# 8_Conectors.net
KiCad netlist of a schematic drawn in Altium Designer
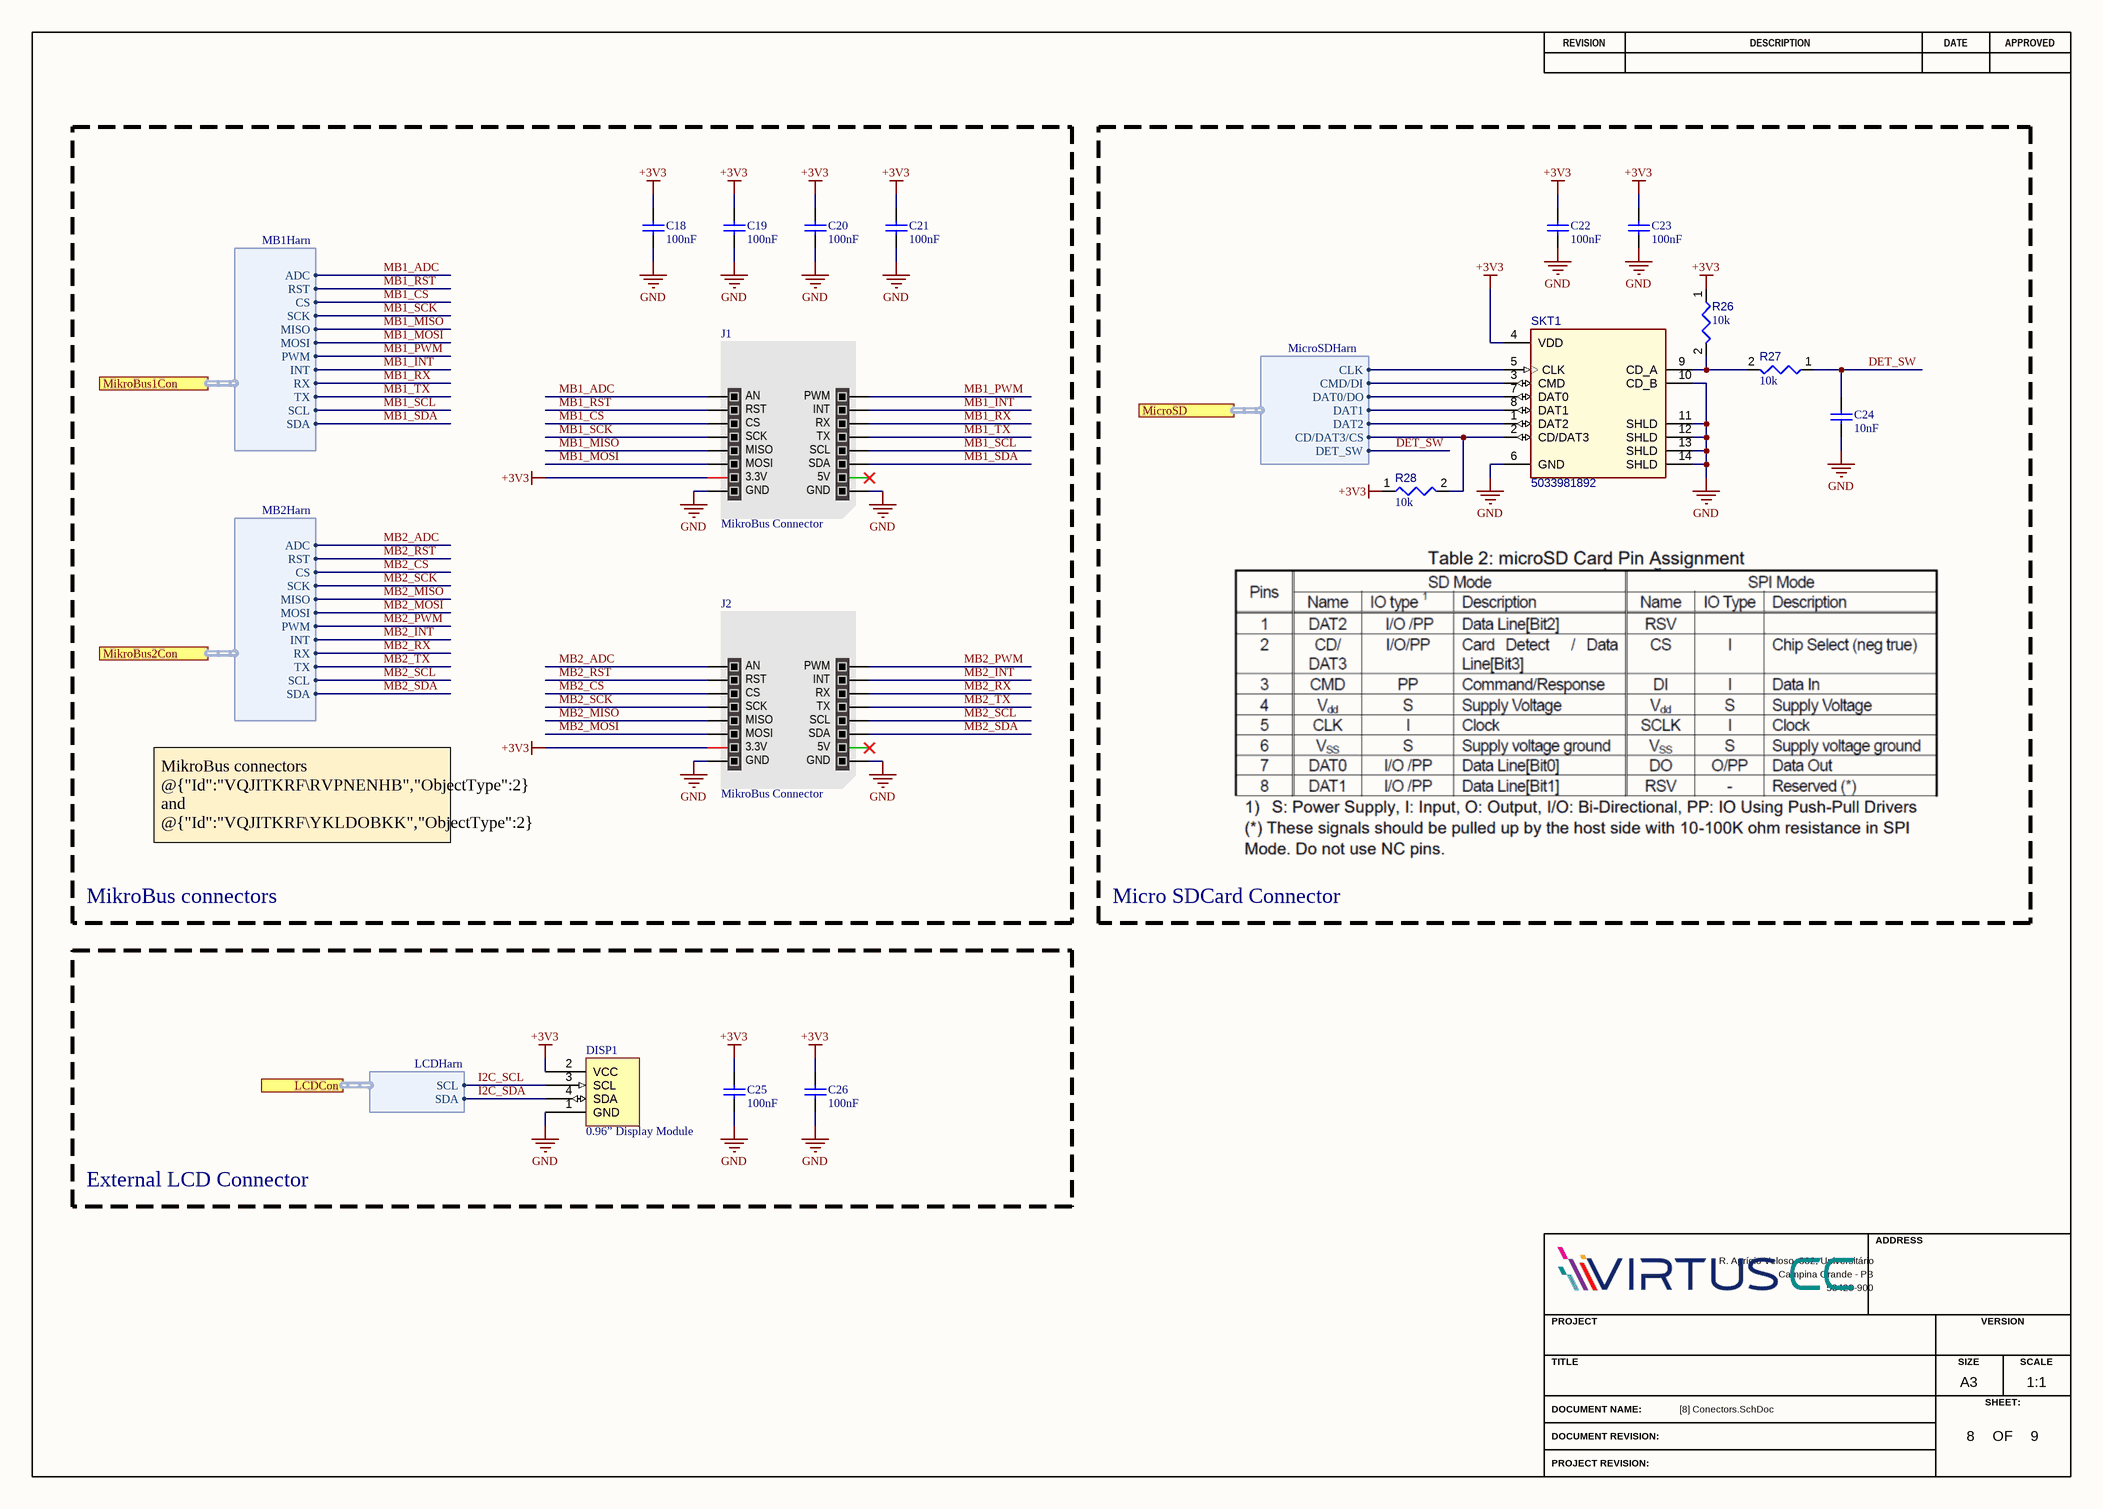
[diagram p0: [8] Conectors.SchDoc]

(export (version "E")
  (design (tool "Eeschema 10.0.6"))
  (components
    (comp (ref "C18")
      (value "100nF")
      (footprint "CAPC0603(1608)100_L")
      (description "Multilayer Ceramic Capacitor, 0.1 uF, 16 V, ± 20%, X7R, 0603 [1608 Metric]")
      (fields (field (name "TOLERANCE") "20%") (field (name "Comment") "VJ0603Y104MXJCW1BC"))
      (libsource (lib "UFCG - Universidade Federal de Campina Grande") (part "CAP"))
    )
    (comp (ref "C19")
      (value "100nF")
      (footprint "CAPC0603(1608)100_L")
      (description "Multilayer Ceramic Capacitor, 0.1 uF, 16 V, ± 20%, X7R, 0603 [1608 Metric]")
      (fields (field (name "TOLERANCE") "20%") (field (name "Comment") "VJ0603Y104MXJCW1BC"))
      (libsource (lib "UFCG - Universidade Federal de Campina Grande") (part "CAP"))
    )
    (comp (ref "C20")
      (value "100nF")
      (footprint "CAPC0603(1608)100_L")
      (description "Multilayer Ceramic Capacitor, 0.1 uF, 16 V, ± 20%, X7R, 0603 [1608 Metric]")
      (fields (field (name "TOLERANCE") "20%") (field (name "Comment") "VJ0603Y104MXJCW1BC"))
      (libsource (lib "UFCG - Universidade Federal de Campina Grande") (part "CAP"))
    )
    (comp (ref "C21")
      (value "100nF")
      (footprint "CAPC0603(1608)100_L")
      (description "Multilayer Ceramic Capacitor, 0.1 uF, 16 V, ± 20%, X7R, 0603 [1608 Metric]")
      (fields (field (name "TOLERANCE") "20%") (field (name "Comment") "VJ0603Y104MXJCW1BC"))
      (libsource (lib "UFCG - Universidade Federal de Campina Grande") (part "CAP"))
    )
    (comp (ref "C22")
      (value "100nF")
      (footprint "CAPC0603(1608)100_L")
      (description "Multilayer Ceramic Capacitor, 0.1 uF, 16 V, ± 20%, X7R, 0603 [1608 Metric]")
      (fields (field (name "TOLERANCE") "20%") (field (name "Comment") "VJ0603Y104MXJCW1BC"))
      (libsource (lib "UFCG - Universidade Federal de Campina Grande") (part "CAP"))
    )
    (comp (ref "C23")
      (value "100nF")
      (footprint "CAPC0603(1608)100_L")
      (description "Multilayer Ceramic Capacitor, 0.1 uF, 16 V, ± 20%, X7R, 0603 [1608 Metric]")
      (fields (field (name "TOLERANCE") "20%") (field (name "Comment") "VJ0603Y104MXJCW1BC"))
      (libsource (lib "UFCG - Universidade Federal de Campina Grande") (part "CAP"))
    )
    (comp (ref "C24")
      (value "10nF")
      (footprint "CAPC0603(1608)100_L")
      (description "Multilayer Ceramic Capacitor, 0.01 uF, 50 V, ± 10%, X7R, 0603 [1608 Metric]")
      (fields (field (name "VOLTAGE") "50V") (field (name "TOLERANCE") "10%"))
      (libsource (lib "UFCG - Universidade Federal de Campina Grande") (part "CAP"))
    )
    (comp (ref "C25")
      (value "100nF")
      (footprint "CAPC0603(1608)100_L")
      (description "Multilayer Ceramic Capacitor, 0.1 uF, 16 V, ± 20%, X7R, 0603 [1608 Metric]")
      (fields (field (name "TOLERANCE") "20%") (field (name "Comment") "VJ0603Y104MXJCW1BC"))
      (libsource (lib "UFCG - Universidade Federal de Campina Grande") (part "CAP"))
    )
    (comp (ref "C26")
      (value "100nF")
      (footprint "CAPC0603(1608)100_L")
      (description "Multilayer Ceramic Capacitor, 0.1 uF, 16 V, ± 20%, X7R, 0603 [1608 Metric]")
      (fields (field (name "TOLERANCE") "20%") (field (name "Comment") "VJ0603Y104MXJCW1BC"))
      (libsource (lib "UFCG - Universidade Federal de Campina Grande") (part "CAP"))
    )
    (comp (ref "DISP1")
      (value "0.96” Display Module")
      (footprint "New footprint 1")
      (description "0.96 Inch I2C OLED Display Module")
      (libsource (lib "UFCG - Universidade Federal de Campina Grande") (part "0.96{dblquote} Display"))
    )
    (comp (ref "J1")
      (value "MikroBus Connector")
      (footprint "New footprint 1")
      (description "MikroBus shield pico")
      (libsource (lib "UFCG - Universidade Federal de Campina Grande") (part "MikroBus connector"))
    )
    (comp (ref "J2")
      (value "MikroBus Connector")
      (footprint "New footprint 1")
      (description "MikroBus shield pico")
      (libsource (lib "UFCG - Universidade Federal de Campina Grande") (part "MikroBus connector"))
    )
    (comp (ref "R26")
      (value "10k")
      (footprint "RESC0603(1608)_L")
      (description "Chip Resistor, 10 KOhm, +/- 1%, 01 W, -55 to 155 degC, 0603 (1608 Metric)")
      (fields (field (name "POWER") "100mW") (field (name "TOLERANCE") "1%"))
      (libsource (lib "UFCG - Universidade Federal de Campina Grande") (part "RES-2"))
    )
    (comp (ref "R27")
      (value "10k")
      (footprint "RESC0603(1608)_L")
      (description "Chip Resistor, 10 KOhm, +/- 1%, 01 W, -55 to 155 degC, 0603 (1608 Metric)")
      (fields (field (name "POWER") "100mW") (field (name "TOLERANCE") "1%"))
      (libsource (lib "UFCG - Universidade Federal de Campina Grande") (part "RES-2"))
    )
    (comp (ref "R28")
      (value "10k")
      (footprint "RESC0603(1608)_L")
      (description "Chip Resistor, 10 KOhm, +/- 1%, 01 W, -55 to 155 degC, 0603 (1608 Metric)")
      (fields (field (name "POWER") "100mW") (field (name "TOLERANCE") "1%"))
      (libsource (lib "UFCG - Universidade Federal de Campina Grande") (part "RES-2"))
    )
    (comp (ref "SKT1")
      (value "5033981892")
      (footprint "MOLX-5033981892_V")
      (libsource (lib "UFCG - Universidade Federal de Campina Grande") (part "CMP-00040-6"))
    )
  )
  (nets
    (net (code "5") (name "+3V3") (class "Default")
      (node (ref "C18") (pin "2") (pinfunction "2_2") (pintype "passive"))
      (node (ref "C19") (pin "2") (pinfunction "2_2") (pintype "passive"))
      (node (ref "C20") (pin "2") (pinfunction "2_2") (pintype "passive"))
      (node (ref "C21") (pin "2") (pinfunction "2_2") (pintype "passive"))
      (node (ref "C22") (pin "2") (pinfunction "2_2") (pintype "passive"))
      (node (ref "C23") (pin "2") (pinfunction "2_2") (pintype "passive"))
      (node (ref "C25") (pin "2") (pinfunction "2_2") (pintype "passive"))
      (node (ref "C26") (pin "2") (pinfunction "2_2") (pintype "passive"))
      (node (ref "DISP1") (pin "2") (pinfunction "VCC_2") (pintype "power_in"))
      (node (ref "J1") (pin "7") (pinfunction "3.3V_7") (pintype "passive"))
      (node (ref "J2") (pin "7") (pinfunction "3.3V_7") (pintype "passive"))
      (node (ref "R26") (pin "1") (pinfunction "1_1") (pintype "passive"))
      (node (ref "R28") (pin "1") (pinfunction "1_1") (pintype "passive"))
      (node (ref "SKT1") (pin "4") (pinfunction "VDD_4") (pintype "power_in"))
    )
    (net (code "6") (name "/CD{slash}DAT3{slash}CS") (class "Default")
      (node (ref "R28") (pin "2") (pinfunction "2_2") (pintype "passive"))
      (node (ref "SKT1") (pin "2") (pinfunction "CD/DAT3_2") (pintype "bidirectional"))
    )
    (net (code "7") (name "/CLK") (class "Default")
      (node (ref "SKT1") (pin "5") (pinfunction "CLK_5") (pintype "input"))
    )
    (net (code "8") (name "/CMD{slash}DI") (class "Default")
      (node (ref "SKT1") (pin "3") (pinfunction "CMD_3") (pintype "bidirectional"))
    )
    (net (code "9") (name "/DAT0{slash}DO") (class "Default")
      (node (ref "SKT1") (pin "7") (pinfunction "DAT0_7") (pintype "bidirectional"))
    )
    (net (code "10") (name "/DAT1") (class "Default")
      (node (ref "SKT1") (pin "8") (pinfunction "DAT1_8") (pintype "bidirectional"))
    )
    (net (code "11") (name "/DAT2") (class "Default")
      (node (ref "SKT1") (pin "1") (pinfunction "DAT2_1") (pintype "bidirectional"))
    )
    (net (code "12") (name "/DET_SW") (class "Default")
      (node (ref "C24") (pin "2") (pinfunction "2_2") (pintype "passive"))
      (node (ref "R27") (pin "1") (pinfunction "1_1") (pintype "passive"))
    )
    (net (code "13") (name "/I2C_SCL") (class "Default")
      (node (ref "DISP1") (pin "3") (pinfunction "SCL_3") (pintype "input"))
    )
    (net (code "14") (name "/I2C_SDA") (class "Default")
      (node (ref "DISP1") (pin "4") (pinfunction "SDA_4") (pintype "bidirectional"))
    )
    (net (code "15") (name "/MB1_ADC") (class "Default")
      (node (ref "J1") (pin "1") (pinfunction "AN_1") (pintype "passive"))
    )
    (net (code "16") (name "/MB1_CS") (class "Default")
      (node (ref "J1") (pin "3") (pinfunction "CS_3") (pintype "passive"))
    )
    (net (code "17") (name "/MB1_INT") (class "Default")
      (node (ref "J1") (pin "15") (pinfunction "INT_15") (pintype "passive"))
    )
    (net (code "18") (name "/MB1_MISO") (class "Default")
      (node (ref "J1") (pin "5") (pinfunction "MISO_5") (pintype "passive"))
    )
    (net (code "19") (name "/MB1_MOSI") (class "Default")
      (node (ref "J1") (pin "6") (pinfunction "MOSI_6") (pintype "passive"))
    )
    (net (code "20") (name "/MB1_PWM") (class "Default")
      (node (ref "J1") (pin "16") (pinfunction "PWM_16") (pintype "passive"))
    )
    (net (code "21") (name "/MB1_RST") (class "Default")
      (node (ref "J1") (pin "2") (pinfunction "RST_2") (pintype "passive"))
    )
    (net (code "22") (name "/MB1_RX") (class "Default")
      (node (ref "J1") (pin "14") (pinfunction "RX_14") (pintype "passive"))
    )
    (net (code "23") (name "/MB1_SCK") (class "Default")
      (node (ref "J1") (pin "4") (pinfunction "SCK_4") (pintype "passive"))
    )
    (net (code "24") (name "/MB1_SCL") (class "Default")
      (node (ref "J1") (pin "12") (pinfunction "SCL_12") (pintype "passive"))
    )
    (net (code "25") (name "/MB1_SDA") (class "Default")
      (node (ref "J1") (pin "11") (pinfunction "SDA_11") (pintype "passive"))
    )
    (net (code "26") (name "/MB1_TX") (class "Default")
      (node (ref "J1") (pin "13") (pinfunction "TX_13") (pintype "passive"))
    )
    (net (code "27") (name "/MB2_ADC") (class "Default")
      (node (ref "J2") (pin "1") (pinfunction "AN_1") (pintype "passive"))
    )
    (net (code "28") (name "/MB2_CS") (class "Default")
      (node (ref "J2") (pin "3") (pinfunction "CS_3") (pintype "passive"))
    )
    (net (code "29") (name "/MB2_INT") (class "Default")
      (node (ref "J2") (pin "15") (pinfunction "INT_15") (pintype "passive"))
    )
    (net (code "30") (name "/MB2_MISO") (class "Default")
      (node (ref "J2") (pin "5") (pinfunction "MISO_5") (pintype "passive"))
    )
    (net (code "31") (name "/MB2_MOSI") (class "Default")
      (node (ref "J2") (pin "6") (pinfunction "MOSI_6") (pintype "passive"))
    )
    (net (code "32") (name "/MB2_PWM") (class "Default")
      (node (ref "J2") (pin "16") (pinfunction "PWM_16") (pintype "passive"))
    )
    (net (code "33") (name "/MB2_RST") (class "Default")
      (node (ref "J2") (pin "2") (pinfunction "RST_2") (pintype "passive"))
    )
    (net (code "34") (name "/MB2_RX") (class "Default")
      (node (ref "J2") (pin "14") (pinfunction "RX_14") (pintype "passive"))
    )
    (net (code "35") (name "/MB2_SCK") (class "Default")
      (node (ref "J2") (pin "4") (pinfunction "SCK_4") (pintype "passive"))
    )
    (net (code "36") (name "/MB2_SCL") (class "Default")
      (node (ref "J2") (pin "12") (pinfunction "SCL_12") (pintype "passive"))
    )
    (net (code "37") (name "/MB2_SDA") (class "Default")
      (node (ref "J2") (pin "11") (pinfunction "SDA_11") (pintype "passive"))
    )
    (net (code "38") (name "/MB2_TX") (class "Default")
      (node (ref "J2") (pin "13") (pinfunction "TX_13") (pintype "passive"))
    )
    (net (code "43") (name "GND") (class "Default")
      (node (ref "C18") (pin "1") (pinfunction "1_1") (pintype "passive"))
      (node (ref "C19") (pin "1") (pinfunction "1_1") (pintype "passive"))
      (node (ref "C20") (pin "1") (pinfunction "1_1") (pintype "passive"))
      (node (ref "C21") (pin "1") (pinfunction "1_1") (pintype "passive"))
      (node (ref "C22") (pin "1") (pinfunction "1_1") (pintype "passive"))
      (node (ref "C23") (pin "1") (pinfunction "1_1") (pintype "passive"))
      (node (ref "C24") (pin "1") (pinfunction "1_1") (pintype "passive"))
      (node (ref "C25") (pin "1") (pinfunction "1_1") (pintype "passive"))
      (node (ref "C26") (pin "1") (pinfunction "1_1") (pintype "passive"))
      (node (ref "DISP1") (pin "1") (pinfunction "GND_1") (pintype "power_in"))
      (node (ref "J1") (pin "8") (pinfunction "GND_8") (pintype "passive"))
      (node (ref "J1") (pin "9") (pinfunction "GND_9") (pintype "passive"))
      (node (ref "J2") (pin "8") (pinfunction "GND_8") (pintype "passive"))
      (node (ref "J2") (pin "9") (pinfunction "GND_9") (pintype "passive"))
      (node (ref "SKT1") (pin "10") (pinfunction "CD_B_10") (pintype "passive"))
      (node (ref "SKT1") (pin "11") (pinfunction "SHLD_11") (pintype "passive"))
      (node (ref "SKT1") (pin "12") (pinfunction "SHLD_12") (pintype "passive"))
      (node (ref "SKT1") (pin "13") (pinfunction "SHLD_13") (pintype "passive"))
      (node (ref "SKT1") (pin "14") (pinfunction "SHLD_14") (pintype "passive"))
      (node (ref "SKT1") (pin "6") (pinfunction "GND_6") (pintype "passive"))
    )
    (net (code "44") (name "Net-(SKT1-CD_A)") (class "Default")
      (node (ref "R26") (pin "2") (pinfunction "2_2") (pintype "passive"))
      (node (ref "R27") (pin "2") (pinfunction "2_2") (pintype "passive"))
      (node (ref "SKT1") (pin "9") (pinfunction "CD_A_9") (pintype "passive"))
    )
    (net (code "45") (name "unconnected-(J1-5V-Pad10)") (class "Default")
      (node (ref "J1") (pin "10") (pinfunction "5V_10") (pintype "passive+no_connect"))
    )
    (net (code "46") (name "unconnected-(J2-5V-Pad10)") (class "Default")
      (node (ref "J2") (pin "10") (pinfunction "5V_10") (pintype "passive+no_connect"))
    )
  )
)
